# ADCAMP_AD8330.net
KiCad netlist of a schematic drawn in Altium Designer
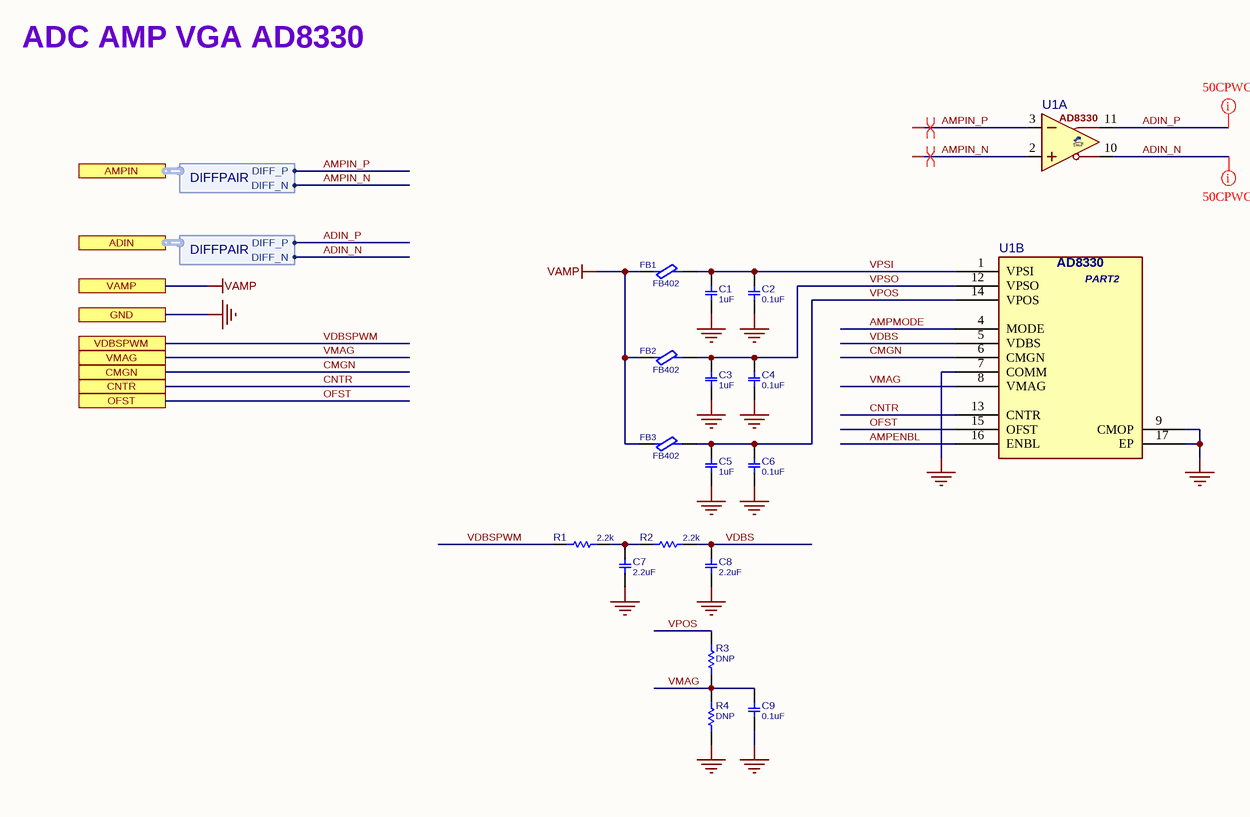
[diagram p0: ADCAMP_AD8330.SchDoc]

(export (version "E")
  (design (tool "Eeschema 10.0.6"))
  (components
    (comp (ref "C1")
      (value "1uF")
      (footprint "C0402")
      (description "CAP, MLCC")
      (libsource (lib "mlcc_smd_passive") (part "CAP_SMD_MLCC_100n50T"))
    )
    (comp (ref "C2")
      (value "0.1uF")
      (footprint "C0402")
      (description "CAP, MLCC")
      (libsource (lib "mlcc_smd_passive") (part "CAP_SMD_MLCC_100n50T"))
    )
    (comp (ref "C3")
      (value "1uF")
      (footprint "C0402")
      (description "CAP, MLCC")
      (libsource (lib "mlcc_smd_passive") (part "CAP_SMD_MLCC_100n50T"))
    )
    (comp (ref "C4")
      (value "0.1uF")
      (footprint "C0402")
      (description "CAP, MLCC")
      (libsource (lib "mlcc_smd_passive") (part "CAP_SMD_MLCC_100n50T"))
    )
    (comp (ref "C5")
      (value "1uF")
      (footprint "C0402")
      (description "CAP, MLCC")
      (libsource (lib "mlcc_smd_passive") (part "CAP_SMD_MLCC_100n50T"))
    )
    (comp (ref "C6")
      (value "0.1uF")
      (footprint "C0402")
      (description "CAP, MLCC")
      (libsource (lib "mlcc_smd_passive") (part "CAP_SMD_MLCC_100n50T"))
    )
    (comp (ref "C7")
      (value "2.2uF")
      (footprint "C0402")
      (description "CAP, MLCC")
      (libsource (lib "mlcc_smd_passive") (part "CAP_SMD_MLCC_100n50T"))
    )
    (comp (ref "C8")
      (value "2.2uF")
      (footprint "C0402")
      (description "CAP, MLCC")
      (libsource (lib "mlcc_smd_passive") (part "CAP_SMD_MLCC_100n50T"))
    )
    (comp (ref "C9")
      (value "0.1uF")
      (footprint "C0402")
      (description "CAP, MLCC")
      (libsource (lib "mlcc_smd_passive") (part "CAP_SMD_MLCC_100n50T"))
    )
    (comp (ref "FB1")
      (value "FB402")
      (footprint "L0402")
      (description "FERRITE_Bead, 0402, 0.5A, 200mOhm, 120@100MHz")
      (fields (field (name "MANF") "MURATA") (field (name "MANF_P#") "BLM15AG121SN1D"))
      (libsource (lib "emi_filter") (part "FBEAD_SMD_BLM15PD121"))
    )
    (comp (ref "FB2")
      (value "FB402")
      (footprint "L0402")
      (description "FERRITE_Bead, 0402, 0.5A, 200mOhm, 120@100MHz")
      (fields (field (name "MANF") "MURATA") (field (name "MANF_P#") "BLM15AG121SN1D"))
      (libsource (lib "emi_filter") (part "FBEAD_SMD_BLM15PD121"))
    )
    (comp (ref "FB3")
      (value "FB402")
      (footprint "L0402")
      (description "FERRITE_Bead, 0402, 0.5A, 200mOhm, 120@100MHz")
      (fields (field (name "MANF") "MURATA") (field (name "MANF_P#") "BLM15AG121SN1D"))
      (libsource (lib "emi_filter") (part "FBEAD_SMD_BLM15PD121"))
    )
    (comp (ref "R1")
      (value "2.2k")
      (footprint "R0402")
      (description "RESISTOR, SMD")
      (fields (field (name "MANF") "Yageo"))
      (libsource (lib "passive_res_smd") (part "RES_SMD_10K_0402"))
    )
    (comp (ref "R2")
      (value "2.2k")
      (footprint "R0402")
      (description "RESISTOR, SMD")
      (fields (field (name "MANF") "Yageo"))
      (libsource (lib "passive_res_smd") (part "RES_SMD_10K_0402"))
    )
    (comp (ref "R3")
      (value "DNP")
      (footprint "R0402")
      (description "RESISTOR, SMD")
      (fields (field (name "MANF") "Yageo"))
      (libsource (lib "passive_res_smd") (part "RES_SMD_10K_0402"))
    )
    (comp (ref "R4")
      (value "DNP")
      (footprint "R0402")
      (description "RESISTOR, SMD")
      (fields (field (name "MANF") "Yageo"))
      (libsource (lib "passive_res_smd") (part "RES_SMD_10K_0402"))
    )
    (comp (ref "U1")
      (value "AD8330")
      (footprint "QFN50_16T_3X3")
      (description "AMP, Differential, Hi-Sp, Fully-Diff, VGA")
      (fields (field (name "MANF") "Analog Devices") (field (name "MANF_P#") "AD8330ACPZ"))
      (libsource (lib "amp") (part "AD8330_QFN16"))
    )
  )
  (nets
    (net (code "2") (name "/ADIN_N") (class "Default")
      (node (ref "U1") (pin "10") (pinfunction "OPLO_10") (pintype "passive"))
    )
    (net (code "3") (name "/ADIN_P") (class "Default")
      (node (ref "U1") (pin "11") (pinfunction "OPHI_11") (pintype "passive"))
    )
    (net (code "4") (name "/AMPENBL") (class "Default")
      (node (ref "U1") (pin "16") (pinfunction "ENBL_16") (pintype "passive"))
    )
    (net (code "5") (name "/AMPIN_N") (class "Default")
      (node (ref "U1") (pin "2") (pinfunction "INHI_2") (pintype "passive"))
    )
    (net (code "6") (name "/AMPIN_P") (class "Default")
      (node (ref "U1") (pin "3") (pinfunction "INLO_3") (pintype "passive"))
    )
    (net (code "7") (name "/AMPMODE") (class "Default")
      (node (ref "U1") (pin "4") (pinfunction "MODE_4") (pintype "passive"))
    )
    (net (code "8") (name "/CMGN") (class "Default")
      (node (ref "U1") (pin "6") (pinfunction "CMGN_6") (pintype "passive"))
    )
    (net (code "9") (name "/CNTR") (class "Default")
      (node (ref "U1") (pin "13") (pinfunction "CNTR_13") (pintype "passive"))
    )
    (net (code "10") (name "/OFST") (class "Default")
      (node (ref "U1") (pin "15") (pinfunction "OFST_15") (pintype "passive"))
    )
    (net (code "11") (name "/VDBS") (class "Default")
      (node (ref "C8") (pin "1") (pinfunction "1_1") (pintype "passive"))
      (node (ref "R2") (pin "2") (pinfunction "2_2") (pintype "passive"))
      (node (ref "U1") (pin "5") (pinfunction "VDBS_5") (pintype "passive"))
    )
    (net (code "12") (name "/VDBSPWM") (class "Default")
      (node (ref "R1") (pin "1") (pinfunction "1_1") (pintype "passive"))
    )
    (net (code "13") (name "/VMAG") (class "Default")
      (node (ref "C9") (pin "1") (pinfunction "1_1") (pintype "passive"))
      (node (ref "R3") (pin "1") (pinfunction "1_1") (pintype "passive"))
      (node (ref "R4") (pin "2") (pinfunction "2_2") (pintype "passive"))
      (node (ref "U1") (pin "8") (pinfunction "VMAG_8") (pintype "passive"))
    )
    (net (code "14") (name "/VPOS") (class "Default")
      (node (ref "C5") (pin "1") (pinfunction "1_1") (pintype "passive"))
      (node (ref "C6") (pin "1") (pinfunction "1_1") (pintype "passive"))
      (node (ref "FB3") (pin "2") (pinfunction "2_2") (pintype "passive"))
      (node (ref "R3") (pin "2") (pinfunction "2_2") (pintype "passive"))
      (node (ref "U1") (pin "14") (pinfunction "VPOS_14") (pintype "power_in"))
    )
    (net (code "15") (name "/VPSI") (class "Default")
      (node (ref "C1") (pin "1") (pinfunction "1_1") (pintype "passive"))
      (node (ref "C2") (pin "1") (pinfunction "1_1") (pintype "passive"))
      (node (ref "FB1") (pin "2") (pinfunction "2_2") (pintype "passive"))
      (node (ref "U1") (pin "1") (pinfunction "VPSI_1") (pintype "power_in"))
    )
    (net (code "16") (name "/VPSO") (class "Default")
      (node (ref "C3") (pin "1") (pinfunction "1_1") (pintype "passive"))
      (node (ref "C4") (pin "1") (pinfunction "1_1") (pintype "passive"))
      (node (ref "FB2") (pin "2") (pinfunction "2_2") (pintype "passive"))
      (node (ref "U1") (pin "12") (pinfunction "VPSO_12") (pintype "power_in"))
    )
    (net (code "18") (name "GND") (class "Default")
      (node (ref "C1") (pin "2") (pinfunction "2_2") (pintype "passive"))
      (node (ref "C2") (pin "2") (pinfunction "2_2") (pintype "passive"))
      (node (ref "C3") (pin "2") (pinfunction "2_2") (pintype "passive"))
      (node (ref "C4") (pin "2") (pinfunction "2_2") (pintype "passive"))
      (node (ref "C5") (pin "2") (pinfunction "2_2") (pintype "passive"))
      (node (ref "C6") (pin "2") (pinfunction "2_2") (pintype "passive"))
      (node (ref "C7") (pin "2") (pinfunction "2_2") (pintype "passive"))
      (node (ref "C8") (pin "2") (pinfunction "2_2") (pintype "passive"))
      (node (ref "C9") (pin "2") (pinfunction "2_2") (pintype "passive"))
      (node (ref "R4") (pin "1") (pinfunction "1_1") (pintype "passive"))
      (node (ref "U1") (pin "17") (pinfunction "EP_17") (pintype "passive"))
      (node (ref "U1") (pin "7") (pinfunction "COMM_7") (pintype "passive"))
      (node (ref "U1") (pin "9") (pinfunction "CMOP_9") (pintype "passive"))
    )
    (net (code "19") (name "Net-(C7-Pad1)") (class "Default")
      (node (ref "C7") (pin "1") (pinfunction "1_1") (pintype "passive"))
      (node (ref "R1") (pin "2") (pinfunction "2_2") (pintype "passive"))
      (node (ref "R2") (pin "1") (pinfunction "1_1") (pintype "passive"))
    )
    (net (code "20") (name "VAMP") (class "Default")
      (node (ref "FB1") (pin "1") (pinfunction "1_1") (pintype "passive"))
      (node (ref "FB2") (pin "1") (pinfunction "1_1") (pintype "passive"))
      (node (ref "FB3") (pin "1") (pinfunction "1_1") (pintype "passive"))
    )
  )
)
